# Noise_Diode.net
KiCad netlist of a schematic drawn in Altium Designer
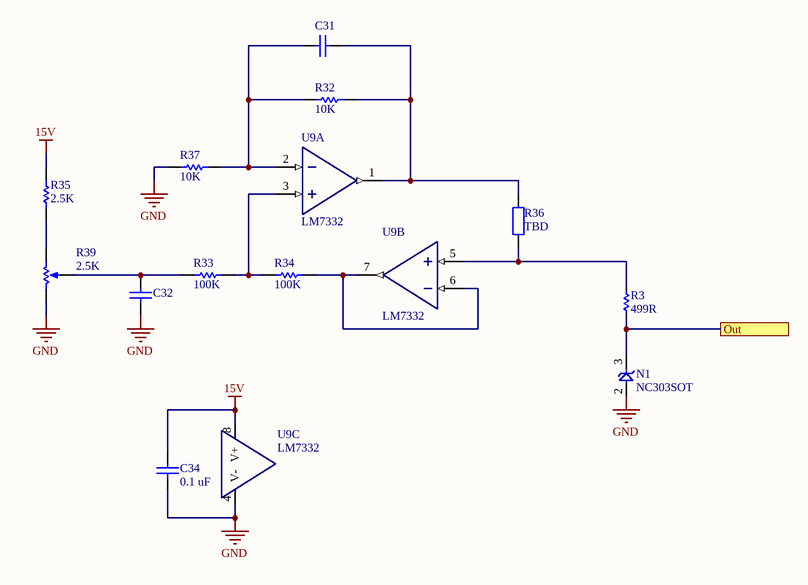
[diagram p0: Noise Diode.SchDoc]

(export (version "E")
  (design (tool "Eeschema 10.0.6"))
  (components
    (comp (ref "C31")
      (value "Cap")
      (footprint "0603C")
      (description "Capacitor")
      (fields (field (name "PUBLISHER") "Altium Limited"))
      (libsource (lib "Miscellaneous Devices") (part "Cap"))
    )
    (comp (ref "C32")
      (value "Cap")
      (footprint "0603C")
      (description "Capacitor")
      (fields (field (name "PUBLISHER") "Altium Limited"))
      (libsource (lib "Miscellaneous Devices") (part "Cap"))
    )
    (comp (ref "C34")
      (value "0.1 uF")
      (footprint "0603C")
      (description "Capacitor")
      (fields (field (name "Comment") "Cap") (field (name "PUBLISHER") "Altium Limited"))
      (libsource (lib "Miscellaneous Devices") (part "Cap"))
    )
    (comp (ref "N1")
      (value "NC303SOT")
      (footprint "SOT323-3AN")
      (description "SMT Noise Diode")
      (libsource (lib "RF Components") (part "NC303SOT"))
    )
    (comp (ref "R3")
      (value "499R")
      (footprint "1206R")
      (description "Semiconductor Resistor")
      (fields (field (name "Comment") "Res Semi Small") (field (name "PUBLISHER") "Altium Limited"))
      (libsource (lib "Miscellaneous Devices") (part "Res Semi Small"))
    )
    (comp (ref "R32")
      (value "10K")
      (footprint "0603R")
      (description "Semiconductor Resistor")
      (fields (field (name "Comment") "Res Semi") (field (name "PUBLISHER") "Altium Limited"))
      (libsource (lib "Miscellaneous Devices") (part "Res Semi"))
    )
    (comp (ref "R33")
      (value "100K")
      (footprint "0603R")
      (description "Semiconductor Resistor")
      (fields (field (name "Comment") "Res Semi") (field (name "PUBLISHER") "Altium Limited"))
      (libsource (lib "Miscellaneous Devices") (part "Res Semi"))
    )
    (comp (ref "R34")
      (value "100K")
      (footprint "0603R")
      (description "Semiconductor Resistor")
      (fields (field (name "Comment") "Res Semi") (field (name "PUBLISHER") "Altium Limited"))
      (libsource (lib "Miscellaneous Devices") (part "Res Semi"))
    )
    (comp (ref "R35")
      (value "2.5K")
      (footprint "1206R")
      (description "Semiconductor Resistor")
      (fields (field (name "Comment") "Res Semi") (field (name "PUBLISHER") "Altium Limited"))
      (libsource (lib "Miscellaneous Devices") (part "Res Semi"))
    )
    (comp (ref "R36")
      (value "TBD")
      (footprint "1206R")
      (description "Resistor")
      (fields (field (name "Comment") "Res2") (field (name "PUBLISHER") "Altium Limited"))
      (libsource (lib "Miscellaneous Devices") (part "Res2"))
    )
    (comp (ref "R37")
      (value "10K")
      (footprint "0603R")
      (description "Semiconductor Resistor")
      (fields (field (name "Comment") "Res Semi") (field (name "PUBLISHER") "Altium Limited"))
      (libsource (lib "Miscellaneous Devices") (part "Res Semi"))
    )
    (comp (ref "R39")
      (value "2.5K")
      (footprint "Bourns 3269W - 12 Turn SMT Trimpot")
      (description "Potentiometer")
      (fields (field (name "PUBLISHER") "Altium Limited"))
      (libsource (lib "Miscellaneous Devices") (part "RPot"))
    )
    (comp (ref "U9")
      (value "LM7332")
      (footprint "SOIC127P600-8CN")
      (description "Dual Rail-to-Rail Input/Output, 30V, Wide Voltage Range, High Output Operational Amplifier")
      (libsource (lib "DAQ System") (part "LM7332"))
    )
  )
  (nets
    (net (code "1") (name "/Out") (class "Default")
      (node (ref "N1") (pin "3") (pinfunction "C_3") (pintype "passive"))
      (node (ref "R3") (pin "1") (pinfunction "1_1") (pintype "passive"))
    )
    (net (code "2") (name "15V") (class "Default")
      (node (ref "C34") (pin "2") (pinfunction "2_2") (pintype "passive"))
      (node (ref "R35") (pin "2") (pinfunction "2_2") (pintype "passive"))
      (node (ref "U9") (pin "8") (pinfunction "V+_8") (pintype "power_in"))
    )
    (net (code "3") (name "GND") (class "Default")
      (node (ref "C32") (pin "1") (pinfunction "1_1") (pintype "passive"))
      (node (ref "C34") (pin "1") (pinfunction "1_1") (pintype "passive"))
      (node (ref "N1") (pin "2") (pinfunction "A_2") (pintype "passive"))
      (node (ref "R37") (pin "1") (pinfunction "1_1") (pintype "passive"))
      (node (ref "R39") (pin "3") (pinfunction "BOT_3") (pintype "passive"))
      (node (ref "U9") (pin "4") (pinfunction "V-_4") (pintype "power_in"))
    )
    (net (code "4") (name "Net-(R39-TAP)") (class "Default")
      (node (ref "C32") (pin "2") (pinfunction "2_2") (pintype "passive"))
      (node (ref "R33") (pin "1") (pinfunction "1_1") (pintype "passive"))
      (node (ref "R39") (pin "2") (pinfunction "TAP_2") (pintype "passive"))
    )
    (net (code "5") (name "Net-(R39-TOP)") (class "Default")
      (node (ref "R35") (pin "1") (pinfunction "1_1") (pintype "passive"))
      (node (ref "R39") (pin "1") (pinfunction "TOP_1") (pintype "passive"))
    )
    (net (code "6") (name "Net-(U9A-In_A_+)") (class "Default")
      (node (ref "R33") (pin "2") (pinfunction "2_2") (pintype "passive"))
      (node (ref "R34") (pin "1") (pinfunction "1_1") (pintype "passive"))
      (node (ref "U9") (pin "3") (pinfunction "In_A_+_3") (pintype "input"))
    )
    (net (code "7") (name "Net-(U9A-In_A_-)") (class "Default")
      (node (ref "C31") (pin "1") (pinfunction "1_1") (pintype "passive"))
      (node (ref "R32") (pin "1") (pinfunction "1_1") (pintype "passive"))
      (node (ref "R37") (pin "2") (pinfunction "2_2") (pintype "passive"))
      (node (ref "U9") (pin "2") (pinfunction "In_A_-_2") (pintype "input"))
    )
    (net (code "8") (name "Net-(U9A-Out_A)") (class "Default")
      (node (ref "C31") (pin "2") (pinfunction "2_2") (pintype "passive"))
      (node (ref "R32") (pin "2") (pinfunction "2_2") (pintype "passive"))
      (node (ref "R36") (pin "2") (pinfunction "2_2") (pintype "passive"))
      (node (ref "U9") (pin "1") (pinfunction "Out_A_1") (pintype "output"))
    )
    (net (code "9") (name "Net-(U9B-In_B_+)") (class "Default")
      (node (ref "R3") (pin "2") (pinfunction "2_2") (pintype "passive"))
      (node (ref "R36") (pin "1") (pinfunction "1_1") (pintype "passive"))
      (node (ref "U9") (pin "5") (pinfunction "In_B_+_5") (pintype "input"))
    )
    (net (code "10") (name "Net-(U9B-In_B_-)") (class "Default")
      (node (ref "R34") (pin "2") (pinfunction "2_2") (pintype "passive"))
      (node (ref "U9") (pin "6") (pinfunction "In_B_-_6") (pintype "input"))
      (node (ref "U9") (pin "7") (pinfunction "Out_B_7") (pintype "output"))
    )
  )
)
